# ESC_B.net
KiCad netlist of a schematic drawn in Altium Designer
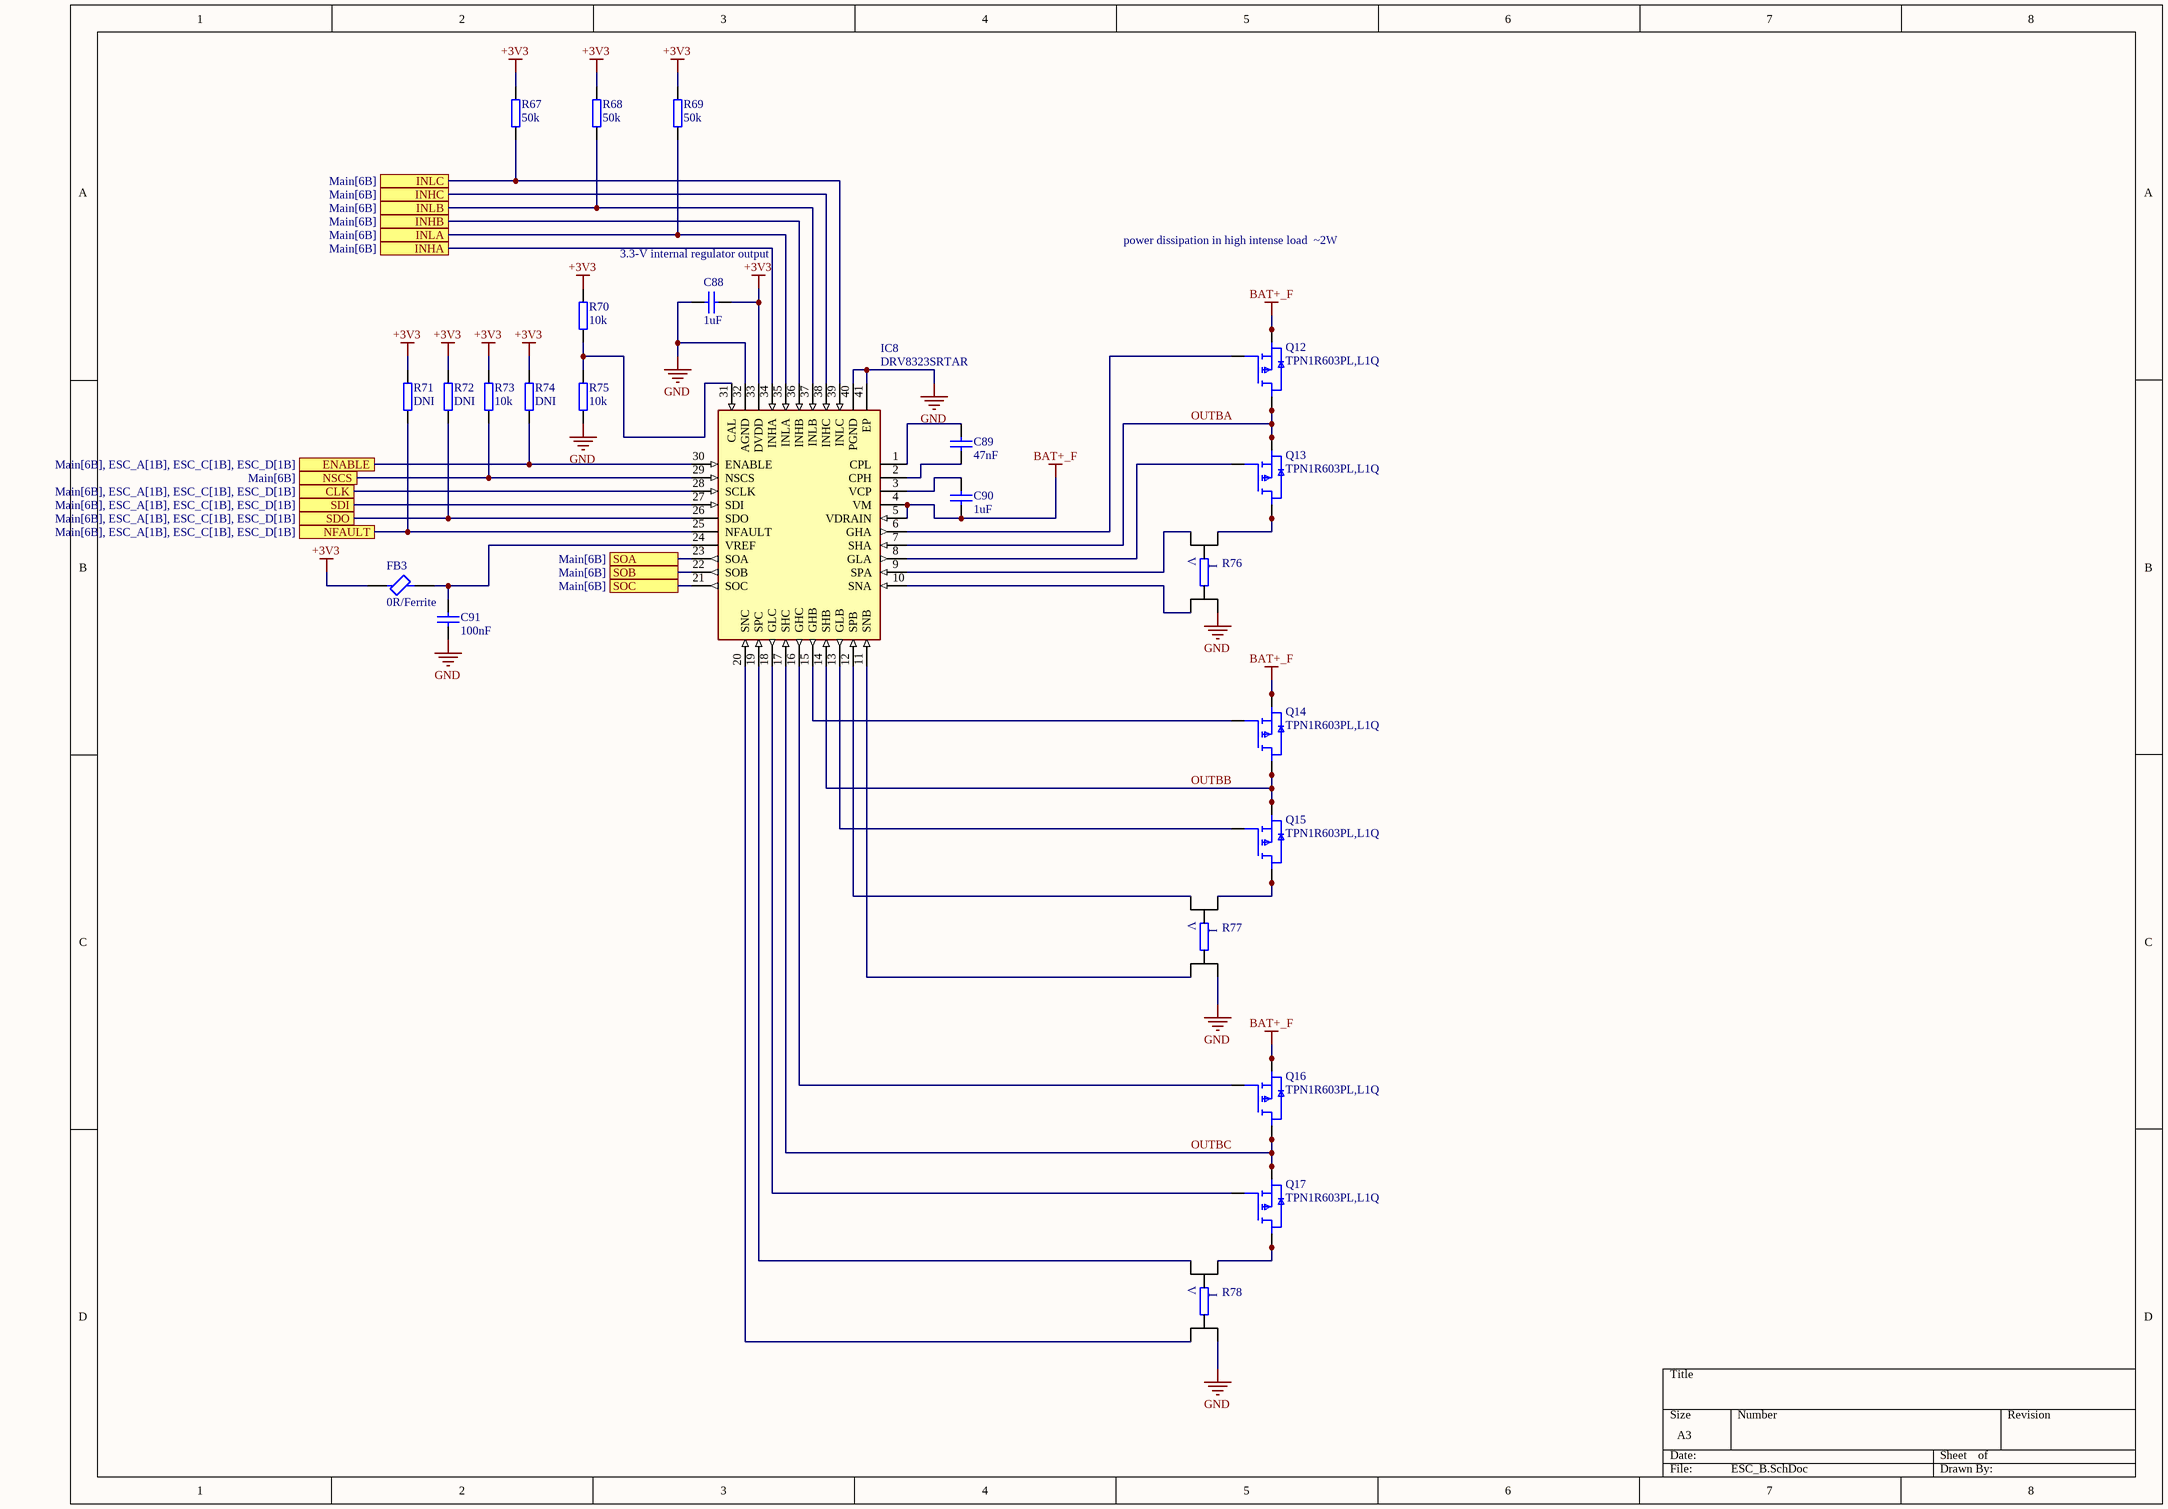
[diagram p0: ESC_B.SchDoc]

(export (version "E")
  (design (tool "Eeschema 10.0.6"))
  (components
    (comp (ref "C88")
      (value "1uF")
      (footprint "CAP0402")
      (fields
        (field (name "VOLTAGE") "50V")
        (field (name "MANUFACTURER_PART_NUMBER") "GRM155R61H105KE05J")
        (field (name "Comment") "Cap0402")
      )
      (libsource (lib "capacitorsSMD") (part "Cap0402"))
    )
    (comp (ref "C89")
      (value "47nF")
      (footprint "CAP0603")
      (description "50V")
      (fields (field (name "Comment") "Cap0603") (field (name "PUBLISHER") "Altium Limited"))
      (libsource (lib "capacitorsSMD") (part "CapSMD0603"))
    )
    (comp (ref "C90")
      (value "1uF")
      (footprint "CAP0603")
      (description "50V")
      (fields (field (name "Comment") "Cap0603") (field (name "PUBLISHER") "Altium Limited"))
      (libsource (lib "capacitorsSMD") (part "CapSMD0603"))
    )
    (comp (ref "C91")
      (value "100nF")
      (footprint "CAP0402")
      (fields
        (field (name "VOLTAGE") "50V")
        (field (name "MANUFACTURER_PART_NUMBER") "GRM155R71H104ME14D")
        (field (name "Comment") "Cap0402")
      )
      (libsource (lib "capacitorsSMD") (part "Cap0402"))
    )
    (comp (ref "FB3")
      (value "0R/Ferrite")
      (footprint "SamacSys:NFZ15SG152SN10B")
      (description "Ferrite Bead")
      (fields
        (field (name "MANUFACTURER_PART_NUMBER") "BLM15PE471SH1D")
        (field (name "MOUSER PART NUMBER") "81-BLM15PE471SH1D")
      )
      (libsource (lib "SamacSys") (part "BLM15PE471SH1D"))
    )
    (comp (ref "IC8")
      (value "DRV8323SRTAR")
      (footprint "SamacSys:QFN50P600X600X80-41N-D")
      (description "Integrated Circuit")
      (fields (field (name "MOUSER PART NUMBER") "595-DRV8323SRTAR"))
      (libsource (lib "*") (part "DRV8323SRTAR"))
    )
    (comp (ref "Q12")
      (value "TPN1R603PL,L1Q")
      (footprint "SamacSys:TPN1R603PLL1Q")
      (description "MOSFET (N-Channel)")
      (fields (field (name "MOUSER PART NUMBER") "757-TPN1R603PLL1Q"))
      (libsource (lib "SamacSys") (part "TPN1R603PL,L1Q"))
    )
    (comp (ref "Q13")
      (value "TPN1R603PL,L1Q")
      (footprint "SamacSys:TPN1R603PLL1Q")
      (description "MOSFET (N-Channel)")
      (fields (field (name "MOUSER PART NUMBER") "757-TPN1R603PLL1Q"))
      (libsource (lib "SamacSys") (part "TPN1R603PL,L1Q"))
    )
    (comp (ref "Q14")
      (value "TPN1R603PL,L1Q")
      (footprint "SamacSys:TPN1R603PLL1Q")
      (description "MOSFET (N-Channel)")
      (fields (field (name "MOUSER PART NUMBER") "757-TPN1R603PLL1Q"))
      (libsource (lib "SamacSys") (part "TPN1R603PL,L1Q"))
    )
    (comp (ref "Q15")
      (value "TPN1R603PL,L1Q")
      (footprint "SamacSys:TPN1R603PLL1Q")
      (description "MOSFET (N-Channel)")
      (fields (field (name "MOUSER PART NUMBER") "757-TPN1R603PLL1Q"))
      (libsource (lib "SamacSys") (part "TPN1R603PL,L1Q"))
    )
    (comp (ref "Q16")
      (value "TPN1R603PL,L1Q")
      (footprint "SamacSys:TPN1R603PLL1Q")
      (description "MOSFET (N-Channel)")
      (fields (field (name "MOUSER PART NUMBER") "757-TPN1R603PLL1Q"))
      (libsource (lib "SamacSys") (part "TPN1R603PL,L1Q"))
    )
    (comp (ref "Q17")
      (value "TPN1R603PL,L1Q")
      (footprint "SamacSys:TPN1R603PLL1Q")
      (description "MOSFET (N-Channel)")
      (fields (field (name "MOUSER PART NUMBER") "757-TPN1R603PLL1Q"))
      (libsource (lib "SamacSys") (part "TPN1R603PL,L1Q"))
    )
    (comp (ref "R67")
      (value "50k")
      (footprint "RES0402")
      (fields (field (name "MANUFACTURER_PART_NUMBER") "TNPW040249K9DEED") (field (name "Comment") "Res0402"))
      (libsource (lib "resistorSMD") (part "Res0402"))
    )
    (comp (ref "R68")
      (value "50k")
      (footprint "RES0402")
      (fields (field (name "MANUFACTURER_PART_NUMBER") "TNPW040249K9DEED") (field (name "Comment") "Res0402"))
      (libsource (lib "resistorSMD") (part "Res0402"))
    )
    (comp (ref "R69")
      (value "50k")
      (footprint "RES0402")
      (fields (field (name "MANUFACTURER_PART_NUMBER") "TNPW040249K9DEED") (field (name "Comment") "Res0402"))
      (libsource (lib "resistorSMD") (part "Res0402"))
    )
    (comp (ref "R70")
      (value "10k")
      (footprint "RES0402")
      (fields (field (name "MANUFACTURER_PART_NUMBER") "ERA-2AED103X") (field (name "Comment") "Res0402"))
      (libsource (lib "resistorSMD") (part "Res0402"))
    )
    (comp (ref "R71")
      (value "DNI")
      (footprint "RES0402")
      (fields (field (name "Comment") "Res0402"))
      (libsource (lib "resistorSMD") (part "Res0402"))
    )
    (comp (ref "R72")
      (value "DNI")
      (footprint "RES0402")
      (fields (field (name "Comment") "Res0402"))
      (libsource (lib "resistorSMD") (part "Res0402"))
    )
    (comp (ref "R73")
      (value "10k")
      (footprint "RES0402")
      (fields (field (name "MANUFACTURER_PART_NUMBER") "ERA-2AED103X") (field (name "Comment") "Res0402"))
      (libsource (lib "resistorSMD") (part "Res0402"))
    )
    (comp (ref "R74")
      (value "DNI")
      (footprint "RES0402")
      (fields (field (name "Comment") "Res0402"))
      (libsource (lib "resistorSMD") (part "Res0402"))
    )
    (comp (ref "R75")
      (value "10k")
      (footprint "RES0402")
      (fields (field (name "MANUFACTURER_PART_NUMBER") "ERA-2AED103X") (field (name "Comment") "Res0402"))
      (libsource (lib "resistorSMD") (part "Res0402"))
    )
    (comp (ref "R76")
      (value "WSK12161L000FEA")
      (footprint "SamacSys:WSK12161L000FEA")
      (description "Resistor")
      (fields
        (field (name "MANUFACTURER_PART_NUMBER") "WSK1216L5000FEA")
        (field (name "MOUSER PART NUMBER") "71-WSK1216L5000FEA")
      )
      (libsource (lib "SamacSys") (part "WSK1216L5000FEA"))
    )
    (comp (ref "R77")
      (value "WSK12161L000FEA")
      (footprint "SamacSys:WSK12161L000FEA")
      (description "Resistor")
      (fields
        (field (name "MANUFACTURER_PART_NUMBER") "WSK1216L5000FEA")
        (field (name "MOUSER PART NUMBER") "71-WSK1216L5000FEA")
      )
      (libsource (lib "SamacSys") (part "WSK1216L5000FEA"))
    )
    (comp (ref "R78")
      (value "WSK12161L000FEA")
      (footprint "SamacSys:WSK12161L000FEA")
      (description "Resistor")
      (fields
        (field (name "MANUFACTURER_PART_NUMBER") "WSK1216L5000FEA")
        (field (name "MOUSER PART NUMBER") "71-WSK1216L5000FEA")
      )
      (libsource (lib "SamacSys") (part "WSK1216L5000FEA"))
    )
  )
  (nets
    (net (code "1") (name "+3V3") (class "Default")
      (node (ref "C88") (pin "2") (pinfunction "2_2") (pintype "passive"))
      (node (ref "FB3") (pin "1") (pinfunction "1_1") (pintype "passive"))
      (node (ref "IC8") (pin "33") (pinfunction "DVDD_33") (pintype "power_in"))
      (node (ref "R67") (pin "2") (pinfunction "2_2") (pintype "passive"))
      (node (ref "R68") (pin "2") (pinfunction "2_2") (pintype "passive"))
      (node (ref "R69") (pin "2") (pinfunction "2_2") (pintype "passive"))
      (node (ref "R70") (pin "2") (pinfunction "2_2") (pintype "passive"))
      (node (ref "R71") (pin "2") (pinfunction "2_2") (pintype "passive"))
      (node (ref "R72") (pin "2") (pinfunction "2_2") (pintype "passive"))
      (node (ref "R73") (pin "2") (pinfunction "2_2") (pintype "passive"))
      (node (ref "R74") (pin "2") (pinfunction "2_2") (pintype "passive"))
    )
    (net (code "2") (name "/CLK") (class "Default")
      (node (ref "IC8") (pin "28") (pinfunction "SCLK_28") (pintype "input"))
    )
    (net (code "3") (name "/ENABLE") (class "Default")
      (node (ref "IC8") (pin "30") (pinfunction "ENABLE_30") (pintype "input"))
      (node (ref "R74") (pin "1") (pinfunction "1_1") (pintype "passive"))
    )
    (net (code "4") (name "/INHA") (class "Default")
      (node (ref "IC8") (pin "34") (pinfunction "INHA_34") (pintype "input"))
    )
    (net (code "5") (name "/INHB") (class "Default")
      (node (ref "IC8") (pin "36") (pinfunction "INHB_36") (pintype "input"))
    )
    (net (code "6") (name "/INHC") (class "Default")
      (node (ref "IC8") (pin "38") (pinfunction "INHC_38") (pintype "input"))
    )
    (net (code "7") (name "/INLA") (class "Default")
      (node (ref "IC8") (pin "35") (pinfunction "INLA_35") (pintype "input"))
      (node (ref "R69") (pin "1") (pinfunction "1_1") (pintype "passive"))
    )
    (net (code "8") (name "/INLB") (class "Default")
      (node (ref "IC8") (pin "37") (pinfunction "INLB_37") (pintype "input"))
      (node (ref "R68") (pin "1") (pinfunction "1_1") (pintype "passive"))
    )
    (net (code "9") (name "/INLC") (class "Default")
      (node (ref "IC8") (pin "39") (pinfunction "INLC_39") (pintype "input"))
      (node (ref "R67") (pin "1") (pinfunction "1_1") (pintype "passive"))
    )
    (net (code "10") (name "/NFAULT") (class "Default")
      (node (ref "IC8") (pin "25") (pinfunction "NFAULT_25") (pintype "passive"))
      (node (ref "R71") (pin "1") (pinfunction "1_1") (pintype "passive"))
    )
    (net (code "11") (name "/NSCS") (class "Default")
      (node (ref "IC8") (pin "29") (pinfunction "NSCS_29") (pintype "input"))
      (node (ref "R73") (pin "1") (pinfunction "1_1") (pintype "passive"))
    )
    (net (code "12") (name "/OUTBA") (class "Default")
      (node (ref "IC8") (pin "7") (pinfunction "SHA_7") (pintype "input"))
      (node (ref "Q12") (pin "5") (pinfunction "D_1_5") (pintype "passive"))
      (node (ref "Q12") (pin "6") (pinfunction "D_2_6") (pintype "passive"))
      (node (ref "Q12") (pin "7") (pinfunction "D_3_7") (pintype "passive"))
      (node (ref "Q12") (pin "8") (pinfunction "D_4_8") (pintype "passive"))
      (node (ref "Q12") (pin "9") (pinfunction "D_4_9") (pintype "passive"))
      (node (ref "Q13") (pin "1") (pinfunction "S_1_1") (pintype "passive"))
      (node (ref "Q13") (pin "2") (pinfunction "S_2_2") (pintype "passive"))
      (node (ref "Q13") (pin "3") (pinfunction "S_3_3") (pintype "passive"))
    )
    (net (code "13") (name "/OUTBB") (class "Default")
      (node (ref "IC8") (pin "14") (pinfunction "SHB_14") (pintype "input"))
      (node (ref "Q14") (pin "5") (pinfunction "D_1_5") (pintype "passive"))
      (node (ref "Q14") (pin "6") (pinfunction "D_2_6") (pintype "passive"))
      (node (ref "Q14") (pin "7") (pinfunction "D_3_7") (pintype "passive"))
      (node (ref "Q14") (pin "8") (pinfunction "D_4_8") (pintype "passive"))
      (node (ref "Q14") (pin "9") (pinfunction "D_4_9") (pintype "passive"))
      (node (ref "Q15") (pin "1") (pinfunction "S_1_1") (pintype "passive"))
      (node (ref "Q15") (pin "2") (pinfunction "S_2_2") (pintype "passive"))
      (node (ref "Q15") (pin "3") (pinfunction "S_3_3") (pintype "passive"))
    )
    (net (code "14") (name "/OUTBC") (class "Default")
      (node (ref "IC8") (pin "17") (pinfunction "SHC_17") (pintype "input"))
      (node (ref "Q16") (pin "5") (pinfunction "D_1_5") (pintype "passive"))
      (node (ref "Q16") (pin "6") (pinfunction "D_2_6") (pintype "passive"))
      (node (ref "Q16") (pin "7") (pinfunction "D_3_7") (pintype "passive"))
      (node (ref "Q16") (pin "8") (pinfunction "D_4_8") (pintype "passive"))
      (node (ref "Q16") (pin "9") (pinfunction "D_4_9") (pintype "passive"))
      (node (ref "Q17") (pin "1") (pinfunction "S_1_1") (pintype "passive"))
      (node (ref "Q17") (pin "2") (pinfunction "S_2_2") (pintype "passive"))
      (node (ref "Q17") (pin "3") (pinfunction "S_3_3") (pintype "passive"))
    )
    (net (code "15") (name "/SDI") (class "Default")
      (node (ref "IC8") (pin "27") (pinfunction "SDI_27") (pintype "input"))
    )
    (net (code "16") (name "/SDO") (class "Default")
      (node (ref "IC8") (pin "26") (pinfunction "SDO_26") (pintype "passive"))
      (node (ref "R72") (pin "1") (pinfunction "1_1") (pintype "passive"))
    )
    (net (code "17") (name "/SOA") (class "Default")
      (node (ref "IC8") (pin "23") (pinfunction "SOA_23") (pintype "output"))
    )
    (net (code "18") (name "/SOB") (class "Default")
      (node (ref "IC8") (pin "22") (pinfunction "SOB_22") (pintype "output"))
    )
    (net (code "19") (name "/SOC") (class "Default")
      (node (ref "IC8") (pin "21") (pinfunction "SOC_21") (pintype "output"))
    )
    (net (code "20") (name "BAT+_F") (class "Default")
      (node (ref "C90") (pin "1") (pinfunction "1_1") (pintype "passive"))
      (node (ref "IC8") (pin "4") (pinfunction "VM_4") (pintype "power_in"))
      (node (ref "IC8") (pin "5") (pinfunction "VDRAIN_5") (pintype "input"))
      (node (ref "Q12") (pin "1") (pinfunction "S_1_1") (pintype "passive"))
      (node (ref "Q12") (pin "2") (pinfunction "S_2_2") (pintype "passive"))
      (node (ref "Q12") (pin "3") (pinfunction "S_3_3") (pintype "passive"))
      (node (ref "Q14") (pin "1") (pinfunction "S_1_1") (pintype "passive"))
      (node (ref "Q14") (pin "2") (pinfunction "S_2_2") (pintype "passive"))
      (node (ref "Q14") (pin "3") (pinfunction "S_3_3") (pintype "passive"))
      (node (ref "Q16") (pin "1") (pinfunction "S_1_1") (pintype "passive"))
      (node (ref "Q16") (pin "2") (pinfunction "S_2_2") (pintype "passive"))
      (node (ref "Q16") (pin "3") (pinfunction "S_3_3") (pintype "passive"))
    )
    (net (code "21") (name "GND") (class "Default")
      (node (ref "C88") (pin "1") (pinfunction "1_1") (pintype "passive"))
      (node (ref "C91") (pin "1") (pinfunction "1_1") (pintype "passive"))
      (node (ref "IC8") (pin "32") (pinfunction "AGND_32") (pintype "power_in"))
      (node (ref "IC8") (pin "40") (pinfunction "PGND_40") (pintype "power_in"))
      (node (ref "IC8") (pin "41") (pinfunction "EP_41") (pintype "power_in"))
      (node (ref "R75") (pin "1") (pinfunction "1_1") (pintype "passive"))
      (node (ref "R76") (pin "4") (pinfunction "4_4") (pintype "passive"))
      (node (ref "R77") (pin "4") (pinfunction "4_4") (pintype "passive"))
      (node (ref "R78") (pin "4") (pinfunction "4_4") (pintype "passive"))
    )
    (net (code "22") (name "Net-(IC8-CAL)") (class "Default")
      (node (ref "IC8") (pin "31") (pinfunction "CAL_31") (pintype "input"))
      (node (ref "R70") (pin "1") (pinfunction "1_1") (pintype "passive"))
      (node (ref "R75") (pin "2") (pinfunction "2_2") (pintype "passive"))
    )
    (net (code "23") (name "Net-(IC8-CPH)") (class "Default")
      (node (ref "C89") (pin "1") (pinfunction "1_1") (pintype "passive"))
      (node (ref "IC8") (pin "2") (pinfunction "CPH_2") (pintype "power_in"))
    )
    (net (code "24") (name "Net-(IC8-CPL)") (class "Default")
      (node (ref "C89") (pin "2") (pinfunction "2_2") (pintype "passive"))
      (node (ref "IC8") (pin "1") (pinfunction "CPL_1") (pintype "power_in"))
    )
    (net (code "25") (name "Net-(IC8-GHA)") (class "Default")
      (node (ref "IC8") (pin "6") (pinfunction "GHA_6") (pintype "output"))
      (node (ref "Q12") (pin "4") (pinfunction "G_4") (pintype "passive"))
    )
    (net (code "26") (name "Net-(IC8-GHB)") (class "Default")
      (node (ref "IC8") (pin "15") (pinfunction "GHB_15") (pintype "output"))
      (node (ref "Q14") (pin "4") (pinfunction "G_4") (pintype "passive"))
    )
    (net (code "27") (name "Net-(IC8-GHC)") (class "Default")
      (node (ref "IC8") (pin "16") (pinfunction "GHC_16") (pintype "output"))
      (node (ref "Q16") (pin "4") (pinfunction "G_4") (pintype "passive"))
    )
    (net (code "28") (name "Net-(IC8-GLA)") (class "Default")
      (node (ref "IC8") (pin "8") (pinfunction "GLA_8") (pintype "output"))
      (node (ref "Q13") (pin "4") (pinfunction "G_4") (pintype "passive"))
    )
    (net (code "29") (name "Net-(IC8-GLB)") (class "Default")
      (node (ref "IC8") (pin "13") (pinfunction "GLB_13") (pintype "output"))
      (node (ref "Q15") (pin "4") (pinfunction "G_4") (pintype "passive"))
    )
    (net (code "30") (name "Net-(IC8-GLC)") (class "Default")
      (node (ref "IC8") (pin "18") (pinfunction "GLC_18") (pintype "output"))
      (node (ref "Q17") (pin "4") (pinfunction "G_4") (pintype "passive"))
    )
    (net (code "31") (name "Net-(IC8-SNA)") (class "Default")
      (node (ref "IC8") (pin "10") (pinfunction "SNA_10") (pintype "input"))
      (node (ref "R76") (pin "3") (pinfunction "3_3") (pintype "passive"))
    )
    (net (code "32") (name "Net-(IC8-SNB)") (class "Default")
      (node (ref "IC8") (pin "11") (pinfunction "SNB_11") (pintype "input"))
      (node (ref "R77") (pin "3") (pinfunction "3_3") (pintype "passive"))
    )
    (net (code "33") (name "Net-(IC8-SNC)") (class "Default")
      (node (ref "IC8") (pin "20") (pinfunction "SNC_20") (pintype "input"))
      (node (ref "R78") (pin "3") (pinfunction "3_3") (pintype "passive"))
    )
    (net (code "34") (name "Net-(IC8-SPA)") (class "Default")
      (node (ref "IC8") (pin "9") (pinfunction "SPA_9") (pintype "input"))
      (node (ref "R76") (pin "2") (pinfunction "2_2") (pintype "passive"))
    )
    (net (code "35") (name "Net-(IC8-SPB)") (class "Default")
      (node (ref "IC8") (pin "12") (pinfunction "SPB_12") (pintype "input"))
      (node (ref "R77") (pin "2") (pinfunction "2_2") (pintype "passive"))
    )
    (net (code "36") (name "Net-(IC8-SPC)") (class "Default")
      (node (ref "IC8") (pin "19") (pinfunction "SPC_19") (pintype "input"))
      (node (ref "R78") (pin "2") (pinfunction "2_2") (pintype "passive"))
    )
    (net (code "37") (name "Net-(IC8-VCP)") (class "Default")
      (node (ref "C90") (pin "2") (pinfunction "2_2") (pintype "passive"))
      (node (ref "IC8") (pin "3") (pinfunction "VCP_3") (pintype "power_in"))
    )
    (net (code "38") (name "Net-(IC8-VREF)") (class "Default")
      (node (ref "C91") (pin "2") (pinfunction "2_2") (pintype "passive"))
      (node (ref "FB3") (pin "2") (pinfunction "2_2") (pintype "passive"))
      (node (ref "IC8") (pin "24") (pinfunction "VREF_24") (pintype "power_in"))
    )
    (net (code "39") (name "Net-(Q13-D_1)") (class "Default")
      (node (ref "Q13") (pin "5") (pinfunction "D_1_5") (pintype "passive"))
      (node (ref "Q13") (pin "6") (pinfunction "D_2_6") (pintype "passive"))
      (node (ref "Q13") (pin "7") (pinfunction "D_3_7") (pintype "passive"))
      (node (ref "Q13") (pin "8") (pinfunction "D_4_8") (pintype "passive"))
      (node (ref "Q13") (pin "9") (pinfunction "D_4_9") (pintype "passive"))
      (node (ref "R76") (pin "1") (pinfunction "1_1") (pintype "passive"))
    )
    (net (code "40") (name "Net-(Q15-D_1)") (class "Default")
      (node (ref "Q15") (pin "5") (pinfunction "D_1_5") (pintype "passive"))
      (node (ref "Q15") (pin "6") (pinfunction "D_2_6") (pintype "passive"))
      (node (ref "Q15") (pin "7") (pinfunction "D_3_7") (pintype "passive"))
      (node (ref "Q15") (pin "8") (pinfunction "D_4_8") (pintype "passive"))
      (node (ref "Q15") (pin "9") (pinfunction "D_4_9") (pintype "passive"))
      (node (ref "R77") (pin "1") (pinfunction "1_1") (pintype "passive"))
    )
    (net (code "41") (name "Net-(Q17-D_1)") (class "Default")
      (node (ref "Q17") (pin "5") (pinfunction "D_1_5") (pintype "passive"))
      (node (ref "Q17") (pin "6") (pinfunction "D_2_6") (pintype "passive"))
      (node (ref "Q17") (pin "7") (pinfunction "D_3_7") (pintype "passive"))
      (node (ref "Q17") (pin "8") (pinfunction "D_4_8") (pintype "passive"))
      (node (ref "Q17") (pin "9") (pinfunction "D_4_9") (pintype "passive"))
      (node (ref "R78") (pin "1") (pinfunction "1_1") (pintype "passive"))
    )
  )
)
